# X_TRACK_MCU_V3_1.net
KiCad netlist of a schematic drawn in Altium Designer
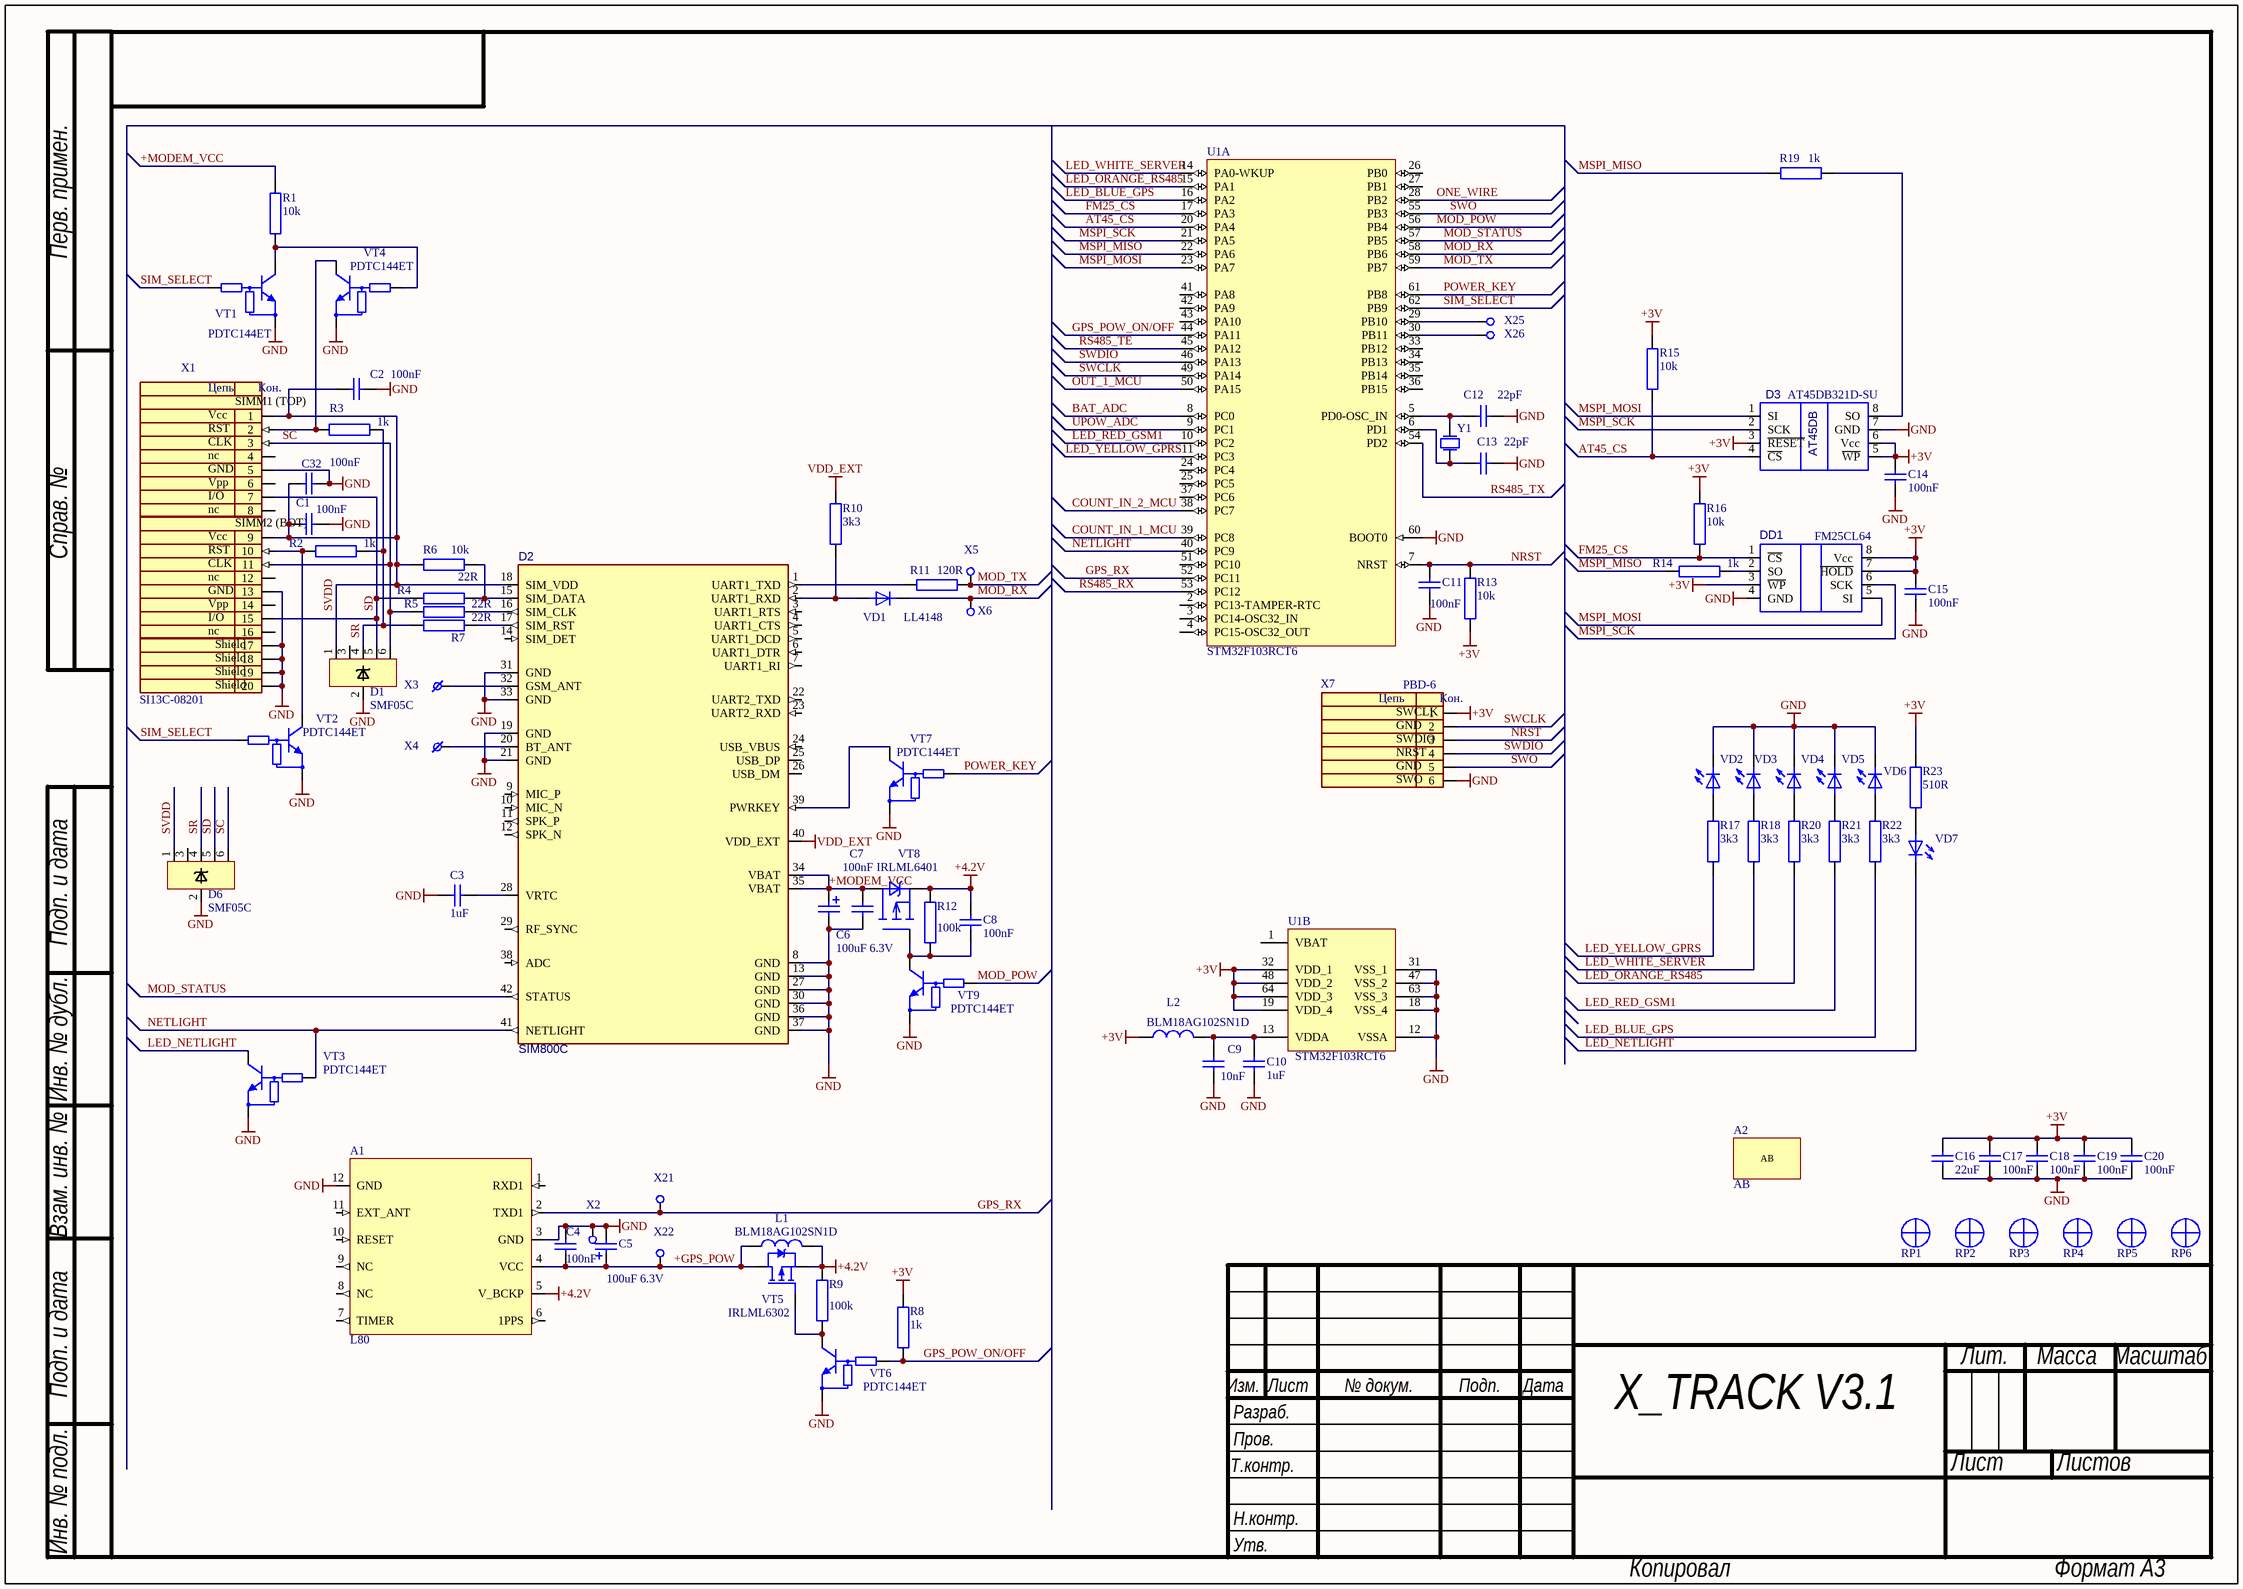
[diagram p0: X_TRACK_MCU V3.1.SchDoc]

(export (version "E")
  (design (tool "Eeschema 10.0.6"))
  (components
    (comp (ref "A1")
      (value "L80")
      (footprint "L80")
      (description "Quectel  Slim GPS Module  Integrated Patch Antenna")
      (fields (field (name "MANUFACTURER") "Quectel"))
      (libsource (lib "Ethernet_new_v000") (part "L80"))
    )
    (comp (ref "A2") (value "AB") (footprint "AB") (libsource (lib "Ethernet_new_v000") (part "AB")))
    (comp (ref "C1")
      (value "100nF")
      (footprint "CC0805")
      (description "Capacitor SMD 0805 X7R 100nF 20% 50V")
      (fields (field (name "MANUFACTURER") "Hitano") (field (name "Comment") "CC0805_100nF"))
      (libsource (lib "Ethernet_new_v000") (part "CC0805_100nF"))
    )
    (comp (ref "C2")
      (value "100nF")
      (footprint "CC0603")
      (description "Capacitor SMD 0603 X7R 100nF 20% 50V")
      (fields (field (name "MANUFACTURER") "Hitano") (field (name "Comment") "CC0603_100nF"))
      (libsource (lib "Ethernet_new_v000") (part "CC0603_100nF"))
    )
    (comp (ref "C3")
      (value "1uF")
      (footprint "CC0603")
      (description "Capacitor SMD 0603 X7R 1uF 20% 10V")
      (fields (field (name "MANUFACTURER") "Hitano") (field (name "Comment") "CC0603_1uF"))
      (libsource (lib "Ethernet_new_v000") (part "CC0603_1uF"))
    )
    (comp (ref "C4")
      (value "100nF")
      (footprint "CC0603")
      (description "Capacitor SMD 0603 X7R 100nF 20% 50V")
      (fields (field (name "MANUFACTURER") "Hitano") (field (name "Comment") "CC0603_100nF"))
      (libsource (lib "Ethernet_new_v000") (part "CC0603_100nF"))
    )
    (comp (ref "C5")
      (value "100uF 6.3V")
      (footprint "6032_TC")
      (description "Capacitor tantall")
      (fields (field (name "MANUFACTURER") "AVX") (field (name "Comment") "C_TAJ 100uF 6.3V C"))
      (libsource (lib "Ethernet_new_v000") (part "C_TAJ 100uF 6.3V C"))
    )
    (comp (ref "C6")
      (value "100uF 6.3V")
      (footprint "6032_TC")
      (description "Capacitor tantall")
      (fields (field (name "MANUFACTURER") "AVX") (field (name "Comment") "C_TAJ 100uF 6.3V C"))
      (libsource (lib "Ethernet_new_v000") (part "C_TAJ 100uF 6.3V C"))
    )
    (comp (ref "C7")
      (value "100nF")
      (footprint "CC0603")
      (description "Capacitor SMD 0603 X7R 100nF 20% 50V")
      (fields (field (name "MANUFACTURER") "Hitano") (field (name "Comment") "CC0603_100nF"))
      (libsource (lib "Ethernet_new_v000") (part "CC0603_100nF"))
    )
    (comp (ref "C8")
      (value "100nF")
      (footprint "CC0603")
      (description "Capacitor SMD 0603 X7R 100nF 20% 50V")
      (fields (field (name "MANUFACTURER") "Hitano") (field (name "Comment") "CC0603_100nF"))
      (libsource (lib "Ethernet_new_v000") (part "CC0603_100nF"))
    )
    (comp (ref "C9")
      (value "10nF")
      (footprint "CC0603")
      (description "Capacitor SMD 0603 X7R 10nF 20% 50V")
      (fields (field (name "MANUFACTURER") "Hitano") (field (name "Comment") "CC0603_10nF"))
      (libsource (lib "Ethernet_new_v000") (part "CC0603_10nF"))
    )
    (comp (ref "C10")
      (value "1uF")
      (footprint "CC0805")
      (description "Capacitor SMD 0805 Y5V 1uF 20% 16V")
      (fields (field (name "MANUFACTURER") "Hitano") (field (name "Comment") "CC0805_1uF"))
      (libsource (lib "Ethernet_new_v000") (part "CC0805_1uF"))
    )
    (comp (ref "C11")
      (value "100nF")
      (footprint "CC0603")
      (description "Capacitor SMD 0603 X7R 100nF 20% 50V")
      (fields (field (name "MANUFACTURER") "Hitano") (field (name "Comment") "CC0603_100nF"))
      (libsource (lib "Ethernet_new_v000") (part "CC0603_100nF"))
    )
    (comp (ref "C12")
      (value "22pF")
      (footprint "CC0603")
      (description "Capacitor SMD 0603 NPO 22pF 5% 50V")
      (fields (field (name "MANUFACTURER") "Hitano") (field (name "Comment") "CC0603_22pF"))
      (libsource (lib "Ethernet_new_v000") (part "CC0603_22pF"))
    )
    (comp (ref "C13")
      (value "22pF")
      (footprint "CC0603")
      (description "Capacitor SMD 0603 NPO 22pF 5% 50V")
      (fields (field (name "MANUFACTURER") "Hitano") (field (name "Comment") "CC0603_22pF"))
      (libsource (lib "Ethernet_new_v000") (part "CC0603_22pF"))
    )
    (comp (ref "C14")
      (value "100nF")
      (footprint "CC0603")
      (description "Capacitor SMD 0603 X7R 100nF 20% 50V")
      (fields (field (name "MANUFACTURER") "Hitano") (field (name "Comment") "CC0603_100nF"))
      (libsource (lib "Ethernet_new_v000") (part "CC0603_100nF"))
    )
    (comp (ref "C15")
      (value "100nF")
      (footprint "CC0603")
      (description "Capacitor SMD 0603 X7R 100nF 20% 50V")
      (fields (field (name "MANUFACTURER") "Hitano") (field (name "Comment") "CC0603_100nF"))
      (libsource (lib "Ethernet_new_v000") (part "CC0603_100nF"))
    )
    (comp (ref "C16")
      (value "22uF")
      (footprint "CC0805")
      (description "Capacitor SMD 0805 Y5V 10uF 20% 16V")
      (fields (field (name "MANUFACTURER") "Hitano") (field (name "Comment") "CC0805_10uF"))
      (libsource (lib "Ethernet_new_v000") (part "CC0805_10uF"))
    )
    (comp (ref "C17")
      (value "100nF")
      (footprint "CC0603")
      (description "Capacitor SMD 0603 X7R 100nF 20% 50V")
      (fields (field (name "MANUFACTURER") "Hitano") (field (name "Comment") "CC0603_100nF"))
      (libsource (lib "Ethernet_new_v000") (part "CC0603_100nF"))
    )
    (comp (ref "C18")
      (value "100nF")
      (footprint "CC0603")
      (description "Capacitor SMD 0603 X7R 100nF 20% 50V")
      (fields (field (name "MANUFACTURER") "Hitano") (field (name "Comment") "CC0603_100nF"))
      (libsource (lib "Ethernet_new_v000") (part "CC0603_100nF"))
    )
    (comp (ref "C19")
      (value "100nF")
      (footprint "CC0603")
      (description "Capacitor SMD 0603 X7R 100nF 20% 50V")
      (fields (field (name "MANUFACTURER") "Hitano") (field (name "Comment") "CC0603_100nF"))
      (libsource (lib "Ethernet_new_v000") (part "CC0603_100nF"))
    )
    (comp (ref "C20")
      (value "100nF")
      (footprint "CC0603")
      (description "Capacitor SMD 0603 X7R 100nF 20% 50V")
      (fields (field (name "MANUFACTURER") "Hitano") (field (name "Comment") "CC0603_100nF"))
      (libsource (lib "Ethernet_new_v000") (part "CC0603_100nF"))
    )
    (comp (ref "C32")
      (value "100nF")
      (footprint "CC0603")
      (description "Capacitor SMD 0603 X7R 100nF 20% 50V")
      (fields (field (name "MANUFACTURER") "Hitano") (field (name "Comment") "CC0603_100nF"))
      (libsource (lib "Ethernet_new_v000") (part "CC0603_100nF"))
    )
    (comp (ref "D1")
      (value "SMF05C")
      (footprint "sc70-6")
      (description "TVS Diode Array For ESD and Latch-Up Protection")
      (fields (field (name "MANUFACTURER") "Semtech"))
      (libsource (lib "Ethernet_new_v000") (part "SMF05C"))
    )
    (comp (ref "D2")
      (value "SIM800C")
      (footprint "SIM800C")
      (fields (field (name "MANUFACTURER") "SIMCOM"))
      (libsource (lib "Ethernet_new_v000") (part "SIM800C"))
    )
    (comp (ref "D3")
      (value "AT45DB321D-SU")
      (footprint "8S2_N_2")
      (description "AT45DB")
      (libsource (lib "V1.5") (part "AT45DB"))
    )
    (comp (ref "D6")
      (value "SMF05C")
      (footprint "sc70-6")
      (description "TVS Diode Array For ESD and Latch-Up Protection")
      (fields (field (name "MANUFACTURER") "Semtech"))
      (libsource (lib "Ethernet_new_v000") (part "SMF05C"))
    )
    (comp (ref "DD1") (value "FM25CL64") (footprint "SO8") (libsource (lib "X_TRACK V1") (part "FM25CL64")))
    (comp (ref "L1")
      (value "BLM18AG102SN1D")
      (footprint "BLM18")
      (description "SMD inductance 750mA")
      (fields (field (name "MANUFACTURER") "Samsung") (field (name "Comment") "L_CIC10P601NC"))
      (libsource (lib "Ethernet_new_v000") (part "L_CIC10P601NC"))
    )
    (comp (ref "L2")
      (value "BLM18AG102SN1D")
      (footprint "BLM18")
      (description "SMD inductance 750mA")
      (fields (field (name "MANUFACTURER") "Samsung") (field (name "Comment") "L_CIC10P601NC"))
      (libsource (lib "Ethernet_new_v000") (part "L_CIC10P601NC"))
    )
    (comp (ref "R1")
      (value "10k")
      (footprint "RC0603")
      (description "Resistor  SMD RC0603 5% 10k")
      (fields (field (name "MANUFACTURER") "Hitano") (field (name "Comment") "RC0603 10k"))
      (libsource (lib "Ethernet_new_v000") (part "RC0603 10k"))
    )
    (comp (ref "R2")
      (value "1k")
      (footprint "RC0603")
      (description "Resistor  SMD 0603  5% 1k")
      (fields (field (name "MANUFACTURER") "Hitano") (field (name "Comment") "RC0603 1k"))
      (libsource (lib "Ethernet_new_v000") (part "RC0603 1k"))
    )
    (comp (ref "R3")
      (value "1k")
      (footprint "RC0603")
      (description "Resistor  SMD 0603  5% 1k")
      (fields (field (name "MANUFACTURER") "Hitano") (field (name "Comment") "RC0603 1k"))
      (libsource (lib "Ethernet_new_v000") (part "RC0603 1k"))
    )
    (comp (ref "R4")
      (value "22R")
      (footprint "RC0603")
      (description "Resistor  SMD 0603 5% 22R")
      (fields (field (name "MANUFACTURER") "Hitano") (field (name "Comment") "RC0603 22R"))
      (libsource (lib "Ethernet_new_v000") (part "RC0603 22R"))
    )
    (comp (ref "R5")
      (value "22R")
      (footprint "RC0603")
      (description "Resistor  SMD 0603 5% 22R")
      (fields (field (name "MANUFACTURER") "Hitano") (field (name "Comment") "RC0603 22R"))
      (libsource (lib "Ethernet_new_v000") (part "RC0603 22R"))
    )
    (comp (ref "R6")
      (value "10k")
      (footprint "RC0603")
      (description "Resistor  SMD RC0603 5% 10k")
      (fields (field (name "MANUFACTURER") "Hitano") (field (name "Comment") "RC0603 10k"))
      (libsource (lib "Ethernet_new_v000") (part "RC0603 10k"))
    )
    (comp (ref "R7")
      (value "22R")
      (footprint "RC0603")
      (description "Resistor  SMD 0603 5% 22R")
      (fields (field (name "MANUFACTURER") "Hitano") (field (name "Comment") "RC0603 22R"))
      (libsource (lib "Ethernet_new_v000") (part "RC0603 22R"))
    )
    (comp (ref "R8")
      (value "1k")
      (footprint "RC0603")
      (description "Resistor  SMD 0603  5% 1k")
      (fields (field (name "MANUFACTURER") "Hitano") (field (name "Comment") "RC0603 1k"))
      (libsource (lib "Ethernet_new_v000") (part "RC0603 1k"))
    )
    (comp (ref "R9")
      (value "100k")
      (footprint "RC0603")
      (description "Resistor  SMD 0603 5% 100k")
      (fields (field (name "MANUFACTURER") "Hitano") (field (name "Comment") "RC0603 100k"))
      (libsource (lib "Ethernet_new_v000") (part "RC0603 100k"))
    )
    (comp (ref "R10")
      (value "3k3")
      (footprint "RC0603")
      (description "Resistor  SMD RC0603 5% 10k")
      (fields (field (name "MANUFACTURER") "Hitano") (field (name "Comment") "RC0603 10k"))
      (libsource (lib "Ethernet_new_v000") (part "RC0603 10k"))
    )
    (comp (ref "R11")
      (value "120R")
      (footprint "RC0603")
      (description "Resistor  SMD 0603 5% 120R")
      (fields (field (name "MANUFACTURER") "Hitano") (field (name "Comment") "RC0603 120R"))
      (libsource (lib "Ethernet_new_v000") (part "RC0603 120R"))
    )
    (comp (ref "R12")
      (value "100k")
      (footprint "RC0603")
      (description "Resistor  SMD 0603 5% 100k")
      (fields (field (name "MANUFACTURER") "Hitano") (field (name "Comment") "RC0603 100k"))
      (libsource (lib "Ethernet_new_v000") (part "RC0603 100k"))
    )
    (comp (ref "R13")
      (value "10k")
      (footprint "RC0603")
      (description "Resistor  SMD RC0603 5% 10k")
      (fields (field (name "MANUFACTURER") "Hitano") (field (name "Comment") "RC0603 10k"))
      (libsource (lib "Ethernet_new_v000") (part "RC0603 10k"))
    )
    (comp (ref "R14")
      (value "1k")
      (footprint "RC0603")
      (description "Resistor  SMD 0603  5% 1k")
      (fields (field (name "MANUFACTURER") "Hitano") (field (name "Comment") "RC0603 1k"))
      (libsource (lib "Ethernet_new_v000") (part "RC0603 1k"))
    )
    (comp (ref "R15")
      (value "10k")
      (footprint "RC0603")
      (description "Resistor  SMD RC0603 5% 10k")
      (fields (field (name "MANUFACTURER") "Hitano") (field (name "Comment") "RC0603 10k"))
      (libsource (lib "Ethernet_new_v000") (part "RC0603 10k"))
    )
    (comp (ref "R16")
      (value "10k")
      (footprint "RC0603")
      (description "Resistor  SMD RC0603 5% 10k")
      (fields (field (name "MANUFACTURER") "Hitano") (field (name "Comment") "RC0603 10k"))
      (libsource (lib "Ethernet_new_v000") (part "RC0603 10k"))
    )
    (comp (ref "R17")
      (value "3k3")
      (footprint "RC0805")
      (description "Resistor  SMD 0805 5% 1k")
      (fields (field (name "MANUFACTURER") "Hitano") (field (name "Comment") "RC0805 1k"))
      (libsource (lib "Ethernet_new_v000") (part "RC0805 1k"))
    )
    (comp (ref "R18")
      (value "3k3")
      (footprint "RC0603")
      (description "Resistor  SMD 0603 5% 300R")
      (fields (field (name "MANUFACTURER") "Hitano") (field (name "Comment") "RC0603 300R"))
      (libsource (lib "Ethernet_new_v000") (part "RC0603 300R"))
    )
    (comp (ref "R19")
      (value "1k")
      (footprint "RC0603")
      (description "Resistor  SMD 0603  5% 1k")
      (fields (field (name "MANUFACTURER") "Hitano") (field (name "Comment") "RC0603 1k"))
      (libsource (lib "Ethernet_new_v000") (part "RC0603 1k"))
    )
    (comp (ref "R20")
      (value "3k3")
      (footprint "RC0603")
      (description "Resistor  SMD 0603 5% 300R")
      (fields (field (name "MANUFACTURER") "Hitano") (field (name "Comment") "RC0603 300R"))
      (libsource (lib "Ethernet_new_v000") (part "RC0603 300R"))
    )
    (comp (ref "R21")
      (value "3k3")
      (footprint "RC0603")
      (description "Resistor  SMD 0603 5% 300R")
      (fields (field (name "MANUFACTURER") "Hitano") (field (name "Comment") "RC0603 300R"))
      (libsource (lib "Ethernet_new_v000") (part "RC0603 300R"))
    )
    (comp (ref "R22")
      (value "3k3")
      (footprint "RC0603")
      (description "Resistor  SMD 0603 5% 300R")
      (fields (field (name "MANUFACTURER") "Hitano") (field (name "Comment") "RC0603 300R"))
      (libsource (lib "Ethernet_new_v000") (part "RC0603 300R"))
    )
    (comp (ref "R23")
      (value "510R")
      (footprint "RC0603")
      (description "Resistor  SMD 0603 5% 300R")
      (fields (field (name "MANUFACTURER") "Hitano") (field (name "Comment") "RC0603 300R"))
      (libsource (lib "Ethernet_new_v000") (part "RC0603 300R"))
    )
    (comp (ref "RP1")
      (value "Reper point")
      (footprint "REPER_1_2")
      (description "Reper point 1_2 mm")
      (libsource (lib "Ethernet_new_v000") (part "Reper point"))
    )
    (comp (ref "RP2")
      (value "Reper point")
      (footprint "REPER_1_2")
      (description "Reper point 1_2 mm")
      (libsource (lib "Ethernet_new_v000") (part "Reper point"))
    )
    (comp (ref "RP3")
      (value "Reper point")
      (footprint "REPER_1_2")
      (description "Reper point 1_2 mm")
      (libsource (lib "Ethernet_new_v000") (part "Reper point"))
    )
    (comp (ref "RP4")
      (value "Reper point")
      (footprint "REPER_1_2")
      (description "Reper point 1_2 mm")
      (libsource (lib "Ethernet_new_v000") (part "Reper point"))
    )
    (comp (ref "RP5")
      (value "Reper point")
      (footprint "REPER_1_2")
      (description "Reper point 1_2 mm")
      (libsource (lib "Ethernet_new_v000") (part "Reper point"))
    )
    (comp (ref "RP6")
      (value "Reper point")
      (footprint "REPER_1_2")
      (description "Reper point 1_2 mm")
      (libsource (lib "Ethernet_new_v000") (part "Reper point"))
    )
    (comp (ref "U1")
      (value "STM32F103RCT6")
      (footprint "LQFP64_N")
      (libsource (lib "STMicroelectronics STM32 F1") (part "STM32F103RCT6"))
    )
    (comp (ref "VD1")
      (value "LL4148")
      (footprint "SOD80D_C")
      (description "SMD Diod BAS85")
      (fields (field (name "MANUFACTURER") "Philips/NXP") (field (name "Comment") "BAS85"))
      (libsource (lib "Ethernet_new_v000") (part "BAS85"))
    )
    (comp (ref "VD2")
      (value "LED_KP-2012EC(0805)_1")
      (footprint "KP-2012EC")
      (description "2.0mmx1.25mm SMT LED,1.1mm thickness High Efficiency Red")
      (fields (field (name "MANUFACTURER") "Kingbright"))
      (libsource (lib "Ethernet_new_v000") (part "LED_KP-2012EC(0805)_1"))
    )
    (comp (ref "VD3")
      (value "LED_KP-2012EC(0805)_1")
      (footprint "KP-2012EC")
      (description "2.0mmx1.25mm SMT LED,1.1mm thickness High Efficiency Red")
      (fields (field (name "MANUFACTURER") "Kingbright"))
      (libsource (lib "Ethernet_new_v000") (part "LED_KP-2012EC(0805)_1"))
    )
    (comp (ref "VD4")
      (value "LED_KP-2012EC(0805)_1")
      (footprint "KP-2012EC")
      (description "2.0mmx1.25mm SMT LED,1.1mm thickness High Efficiency Red")
      (fields (field (name "MANUFACTURER") "Kingbright"))
      (libsource (lib "Ethernet_new_v000") (part "LED_KP-2012EC(0805)_1"))
    )
    (comp (ref "VD5")
      (value "LED_KP-2012EC(0805)_1")
      (footprint "KP-2012EC")
      (description "2.0mmx1.25mm SMT LED,1.1mm thickness High Efficiency Red")
      (fields (field (name "MANUFACTURER") "Kingbright"))
      (libsource (lib "Ethernet_new_v000") (part "LED_KP-2012EC(0805)_1"))
    )
    (comp (ref "VD6")
      (value "LED_KP-2012EC(0805)_1")
      (footprint "KP-2012EC")
      (description "2.0mmx1.25mm SMT LED,1.1mm thickness High Efficiency Red")
      (fields (field (name "MANUFACTURER") "Kingbright"))
      (libsource (lib "Ethernet_new_v000") (part "LED_KP-2012EC(0805)_1"))
    )
    (comp (ref "VD7")
      (value "LED_KP-2012EC(0805)_1")
      (footprint "KP-2012EC")
      (description "2.0mmx1.25mm SMT LED,1.1mm thickness High Efficiency Red")
      (fields (field (name "MANUFACTURER") "Kingbright"))
      (libsource (lib "Ethernet_new_v000") (part "LED_KP-2012EC(0805)_1"))
    )
    (comp (ref "VT1")
      (value "PDTC144ET")
      (footprint "SOT23")
      (description "NPN Digital transistor with bult-in resistor 2k  100mA/50V")
      (fields (field (name "MANUFACTURER") "NXP Semiconductors") (field (name "Comment") "PDTC123ET"))
      (libsource (lib "") (part "PDTC123ET_1"))
    )
    (comp (ref "VT2")
      (value "PDTC144ET")
      (footprint "SOT23")
      (description "NPN Digital transistor with bult-in resistor 2k  100mA/50V")
      (fields (field (name "MANUFACTURER") "NXP Semiconductors") (field (name "Comment") "PDTC123ET"))
      (libsource (lib "") (part "PDTC123ET_1"))
    )
    (comp (ref "VT3")
      (value "PDTC144ET")
      (footprint "SOT23")
      (description "NPN Digital transistor with bult-in resistor 2k  100mA/50V")
      (fields (field (name "MANUFACTURER") "NXP Semiconductors") (field (name "Comment") "PDTC123ET"))
      (libsource (lib "Ethernet_new_v000") (part "PDTC123ET"))
    )
    (comp (ref "VT4")
      (value "PDTC144ET")
      (footprint "SOT23")
      (description "NPN Digital transistor with bult-in resistor 2k  100mA/50V")
      (fields (field (name "MANUFACTURER") "NXP Semiconductors") (field (name "Comment") "PDTC123ET"))
      (libsource (lib "Ethernet_new_v000") (part "PDTC123ET"))
    )
    (comp (ref "VT5")
      (value "IRLML6302")
      (footprint "SOT23")
      (description "P-Channel Power MOSFET 20V 0.78A(25`C)")
      (fields (field (name "MANUFACTURER") "International Rectifier"))
      (libsource (lib "Ethernet_new_v000") (part "IRLML6302"))
    )
    (comp (ref "VT6")
      (value "PDTC144ET")
      (footprint "SOT23")
      (description "NPN Digital transistor with bult-in resistor 2k  100mA/50V")
      (fields (field (name "MANUFACTURER") "NXP Semiconductors") (field (name "Comment") "PDTC123ET"))
      (libsource (lib "Ethernet_new_v000") (part "PDTC123ET"))
    )
    (comp (ref "VT7")
      (value "PDTC144ET")
      (footprint "SOT23")
      (description "NPN Digital transistor with bult-in resistor 2k  100mA/50V")
      (fields (field (name "MANUFACTURER") "NXP Semiconductors") (field (name "Comment") "PDTC123ET"))
      (libsource (lib "Ethernet_new_v000") (part "PDTC123ET"))
    )
    (comp (ref "VT8") (value "IRLML6401") (footprint "SOT23") (libsource (lib "V1.5") (part "IRLML6401")))
    (comp (ref "VT9")
      (value "PDTC144ET")
      (footprint "SOT23")
      (description "NPN Digital transistor with bult-in resistor 2k  100mA/50V")
      (fields (field (name "MANUFACTURER") "NXP Semiconductors") (field (name "Comment") "PDTC123ET"))
      (libsource (lib "Ethernet_new_v000") (part "PDTC123ET"))
    )
    (comp (ref "X1")
      (value "SI13С-08201")
      (footprint "SI13C-08201")
      (description "Dual SIM Card Connector h=3.0mm max")
      (fields (field (name "MANUFACTURER") "ATOM"))
      (libsource (lib "Ethernet_new_v000") (part "SI13С-08201"))
    )
    (comp (ref "X2")
      (value "Con 1")
      (footprint "TP_0.8/1.5")
      (description "Contact")
      (libsource (lib "Ethernet_new_v000") (part "Con 1"))
    )
    (comp (ref "X3")
      (value "Con_1")
      (footprint "TP_1.5/2.5")
      (description "Contact")
      (libsource (lib "Ethernet_new_v000") (part "Con_1"))
    )
    (comp (ref "X4")
      (value "Con_1")
      (footprint "TP_1/2")
      (description "Contact")
      (libsource (lib "Ethernet_new_v000") (part "Con_1"))
    )
    (comp (ref "X5")
      (value "Con 1")
      (footprint "TP_0.8/1.5")
      (description "Contact")
      (libsource (lib "Ethernet_new_v000") (part "Con 1"))
    )
    (comp (ref "X6")
      (value "Con 1")
      (footprint "TP_0.8/1.5")
      (description "Contact")
      (libsource (lib "Ethernet_new_v000") (part "Con 1"))
    )
    (comp (ref "X7")
      (value "PBD-6")
      (footprint "PLS6")
      (description "CON_1x6")
      (fields (field (name "MANUFACTURER") "Amtek") (field (name "Comment") "CON_1x6_"))
      (libsource (lib "X_TRACK V1") (part "CON_1x6_"))
    )
    (comp (ref "X21")
      (value "Con 1")
      (footprint "TP_0.8/1.5")
      (description "Contact")
      (libsource (lib "Ethernet_new_v000") (part "Con 1"))
    )
    (comp (ref "X22")
      (value "Con 1")
      (footprint "TP_0.8/1.5")
      (description "Contact")
      (libsource (lib "Ethernet_new_v000") (part "Con 1"))
    )
    (comp (ref "X25")
      (value "Con 1")
      (footprint "TP_0.5/1.0 - without silkscreen")
      (description "Contact")
      (libsource (lib "Ethernet_new_v000") (part "Con 1"))
    )
    (comp (ref "X26")
      (value "Con 1")
      (footprint "TP_0.5/1.0 - without silkscreen")
      (description "Contact")
      (libsource (lib "Ethernet_new_v000") (part "Con 1"))
    )
    (comp (ref "Y1")
      (value "XTAL")
      (footprint "CRYSTAL")
      (description "Crystal Oscillator")
      (fields (field (name "MANUFACTURER") "Jauch"))
      (libsource (lib "Ethernet_new_v000") (part "XTAL"))
    )
  )
  (nets
    (net (code "1") (name "+3V") (class "Default")
      (node (ref "C14") (pin "2") (pinfunction "2_2") (pintype "passive"))
      (node (ref "C15") (pin "2") (pinfunction "2_2") (pintype "passive"))
      (node (ref "C16") (pin "2") (pinfunction "2_2") (pintype "passive"))
      (node (ref "C17") (pin "2") (pinfunction "2_2") (pintype "passive"))
      (node (ref "C18") (pin "2") (pinfunction "2_2") (pintype "passive"))
      (node (ref "C19") (pin "2") (pinfunction "2_2") (pintype "passive"))
      (node (ref "C20") (pin "2") (pinfunction "2_2") (pintype "passive"))
      (node (ref "D3") (pin "3") (pinfunction "~{RESET}_3") (pintype "passive"))
      (node (ref "D3") (pin "5") (pinfunction "~{WP}_5") (pintype "passive"))
      (node (ref "D3") (pin "6") (pinfunction "Vcc_6") (pintype "passive"))
      (node (ref "DD1") (pin "3") (pinfunction "~{WP}_3") (pintype "passive"))
      (node (ref "DD1") (pin "7") (pinfunction "~{HOLD}_7") (pintype "passive"))
      (node (ref "DD1") (pin "8") (pinfunction "Vcc_8") (pintype "passive"))
      (node (ref "L2") (pin "1") (pinfunction "1_1") (pintype "passive"))
      (node (ref "R13") (pin "2") (pinfunction "2_2") (pintype "passive"))
      (node (ref "R15") (pin "2") (pinfunction "2_2") (pintype "passive"))
      (node (ref "R16") (pin "2") (pinfunction "2_2") (pintype "passive"))
      (node (ref "R23") (pin "2") (pinfunction "2_2") (pintype "passive"))
      (node (ref "R8") (pin "2") (pinfunction "2_2") (pintype "passive"))
      (node (ref "U1") (pin "19") (pinfunction "VDD_4_19") (pintype "power_in"))
      (node (ref "U1") (pin "32") (pinfunction "VDD_1_32") (pintype "power_in"))
      (node (ref "U1") (pin "48") (pinfunction "VDD_2_48") (pintype "power_in"))
      (node (ref "U1") (pin "64") (pinfunction "VDD_3_64") (pintype "power_in"))
      (node (ref "X7") (pin "1") (pinfunction "1_1") (pintype "passive"))
    )
    (net (code "2") (name "+4.2V") (class "Default")
      (node (ref "A1") (pin "5") (pinfunction "V_BCKP_5") (pintype "power_in"))
      (node (ref "C8") (pin "2") (pinfunction "2_2") (pintype "passive"))
      (node (ref "L1") (pin "2") (pinfunction "2_2") (pintype "passive"))
      (node (ref "R12") (pin "2") (pinfunction "2_2") (pintype "passive"))
      (node (ref "R9") (pin "2") (pinfunction "2_2") (pintype "passive"))
      (node (ref "VT5") (pin "2") (pinfunction "S_2") (pintype "passive"))
      (node (ref "VT8") (pin "2") (pinfunction "S_2") (pintype "passive"))
    )
    (net (code "3") (name "/+GPS_POW") (class "Default")
      (node (ref "A1") (pin "4") (pinfunction "VCC_4") (pintype "power_in"))
      (node (ref "C4") (pin "2") (pinfunction "2_2") (pintype "passive"))
      (node (ref "C5") (pin "1") (pinfunction "1_1") (pintype "passive"))
      (node (ref "L1") (pin "1") (pinfunction "1_1") (pintype "passive"))
      (node (ref "VT5") (pin "3") (pinfunction "D_3") (pintype "passive"))
      (node (ref "X22") (pin "1") (pinfunction "1_1") (pintype "passive"))
    )
    (net (code "4") (name "/+MODEM_VCC") (class "Default")
      (node (ref "C6") (pin "1") (pinfunction "1_1") (pintype "passive"))
      (node (ref "C7") (pin "2") (pinfunction "2_2") (pintype "passive"))
      (node (ref "D2") (pin "34") (pinfunction "VBAT_34") (pintype "power_in"))
      (node (ref "D2") (pin "35") (pinfunction "VBAT_35") (pintype "power_in"))
      (node (ref "R1") (pin "1") (pinfunction "1_1") (pintype "passive"))
      (node (ref "VT8") (pin "3") (pinfunction "D_3") (pintype "passive"))
    )
    (net (code "5") (name "/AT45_CS") (class "Default")
      (node (ref "D3") (pin "4") (pinfunction "~{CS}_4") (pintype "passive"))
      (node (ref "R15") (pin "1") (pinfunction "1_1") (pintype "passive"))
      (node (ref "U1") (pin "20") (pinfunction "PA4_20") (pintype "bidirectional"))
    )
    (net (code "6") (name "/BAT_ADC") (class "Default")
      (node (ref "U1") (pin "8") (pinfunction "PC0_8") (pintype "bidirectional"))
    )
    (net (code "7") (name "/COUNT_IN_1_MCU") (class "Default")
      (node (ref "U1") (pin "39") (pinfunction "PC8_39") (pintype "bidirectional"))
    )
    (net (code "8") (name "/COUNT_IN_2_MCU") (class "Default")
      (node (ref "U1") (pin "38") (pinfunction "PC7_38") (pintype "bidirectional"))
    )
    (net (code "9") (name "/FM25_CS") (class "Default")
      (node (ref "DD1") (pin "1") (pinfunction "~{CS}_1") (pintype "passive"))
      (node (ref "R16") (pin "1") (pinfunction "1_1") (pintype "passive"))
      (node (ref "U1") (pin "17") (pinfunction "PA3_17") (pintype "bidirectional"))
    )
    (net (code "10") (name "/GPS_POW_ON{slash}OFF") (class "Default")
      (node (ref "R8") (pin "1") (pinfunction "1_1") (pintype "passive"))
      (node (ref "U1") (pin "44") (pinfunction "PA11_44") (pintype "bidirectional"))
      (node (ref "VT6") (pin "1") (pinfunction "B_1") (pintype "passive"))
    )
    (net (code "11") (name "/GPS_RX") (class "Default")
      (node (ref "A1") (pin "2") (pinfunction "TXD1_2") (pintype "output"))
      (node (ref "U1") (pin "52") (pinfunction "PC11_52") (pintype "bidirectional"))
      (node (ref "X21") (pin "1") (pinfunction "1_1") (pintype "passive"))
    )
    (net (code "12") (name "/LED_BLUE_GPS") (class "Default")
      (node (ref "R22") (pin "1") (pinfunction "1_1") (pintype "passive"))
      (node (ref "U1") (pin "16") (pinfunction "PA2_16") (pintype "bidirectional"))
    )
    (net (code "13") (name "/LED_NETLIGHT") (class "Default")
      (node (ref "VD7") (pin "2") (pinfunction "K_2") (pintype "passive"))
      (node (ref "VT3") (pin "3") (pinfunction "C_3") (pintype "passive"))
    )
    (net (code "14") (name "/LED_ORANGE_RS485") (class "Default")
      (node (ref "R20") (pin "1") (pinfunction "1_1") (pintype "passive"))
      (node (ref "U1") (pin "15") (pinfunction "PA1_15") (pintype "bidirectional"))
    )
    (net (code "15") (name "/LED_RED_GSM1") (class "Default")
      (node (ref "R21") (pin "1") (pinfunction "1_1") (pintype "passive"))
      (node (ref "U1") (pin "10") (pinfunction "PC2_10") (pintype "bidirectional"))
    )
    (net (code "16") (name "/LED_WHITE_SERVER") (class "Default")
      (node (ref "R18") (pin "1") (pinfunction "1_1") (pintype "passive"))
      (node (ref "U1") (pin "14") (pinfunction "PA0-WKUP_14") (pintype "bidirectional"))
    )
    (net (code "17") (name "/LED_YELLOW_GPRS") (class "Default")
      (node (ref "R17") (pin "1") (pinfunction "1_1") (pintype "passive"))
      (node (ref "U1") (pin "11") (pinfunction "PC3_11") (pintype "bidirectional"))
    )
    (net (code "18") (name "/MOD_POW") (class "Default")
      (node (ref "U1") (pin "56") (pinfunction "PB4_56") (pintype "bidirectional"))
      (node (ref "VT9") (pin "1") (pinfunction "B_1") (pintype "passive"))
    )
    (net (code "19") (name "/MOD_RX") (class "Default")
      (node (ref "U1") (pin "58") (pinfunction "PB6_58") (pintype "bidirectional"))
      (node (ref "VD1") (pin "2") (pinfunction "K_2") (pintype "passive"))
      (node (ref "X6") (pin "1") (pinfunction "1_1") (pintype "passive"))
    )
    (net (code "20") (name "/MOD_STATUS") (class "Default")
      (node (ref "D2") (pin "42") (pinfunction "STATUS_42") (pintype "output"))
      (node (ref "U1") (pin "57") (pinfunction "PB5_57") (pintype "bidirectional"))
    )
    (net (code "21") (name "/MOD_TX") (class "Default")
      (node (ref "R11") (pin "1") (pinfunction "1_1") (pintype "passive"))
      (node (ref "U1") (pin "59") (pinfunction "PB7_59") (pintype "bidirectional"))
      (node (ref "X5") (pin "1") (pinfunction "1_1") (pintype "passive"))
    )
    (net (code "22") (name "/MSPI_MISO") (class "Default")
      (node (ref "R14") (pin "1") (pinfunction "1_1") (pintype "passive"))
      (node (ref "R19") (pin "1") (pinfunction "1_1") (pintype "passive"))
      (node (ref "U1") (pin "22") (pinfunction "PA6_22") (pintype "bidirectional"))
    )
    (net (code "23") (name "/MSPI_MOSI") (class "Default")
      (node (ref "D3") (pin "1") (pinfunction "SI_1") (pintype "passive"))
      (node (ref "DD1") (pin "5") (pinfunction "SI_5") (pintype "passive"))
      (node (ref "U1") (pin "23") (pinfunction "PA7_23") (pintype "bidirectional"))
    )
    (net (code "24") (name "/MSPI_SCK") (class "Default")
      (node (ref "D3") (pin "2") (pinfunction "SCK_2") (pintype "passive"))
      (node (ref "DD1") (pin "6") (pinfunction "SCK_6") (pintype "passive"))
      (node (ref "U1") (pin "21") (pinfunction "PA5_21") (pintype "bidirectional"))
    )
    (net (code "25") (name "/NETLIGHT") (class "Default")
      (node (ref "D2") (pin "41") (pinfunction "NETLIGHT_41") (pintype "output"))
      (node (ref "U1") (pin "40") (pinfunction "PC9_40") (pintype "bidirectional"))
      (node (ref "VT3") (pin "1") (pinfunction "B_1") (pintype "passive"))
    )
    (net (code "26") (name "/NRST") (class "Default")
      (node (ref "C11") (pin "2") (pinfunction "2_2") (pintype "passive"))
      (node (ref "R13") (pin "1") (pinfunction "1_1") (pintype "passive"))
      (node (ref "U1") (pin "7") (pinfunction "NRST_7") (pintype "bidirectional"))
      (node (ref "X7") (pin "3") (pinfunction "3_3") (pintype "passive"))
    )
    (net (code "27") (name "/ONE_WIRE") (class "Default")
      (node (ref "U1") (pin "28") (pinfunction "PB2_28") (pintype "bidirectional"))
    )
    (net (code "28") (name "/OUT_1_MCU") (class "Default")
      (node (ref "U1") (pin "50") (pinfunction "PA15_50") (pintype "bidirectional"))
    )
    (net (code "29") (name "/POWER_KEY") (class "Default")
      (node (ref "U1") (pin "61") (pinfunction "PB8_61") (pintype "bidirectional"))
      (node (ref "VT7") (pin "1") (pinfunction "B_1") (pintype "passive"))
    )
    (net (code "30") (name "/RS485_RX") (class "Default")
      (node (ref "U1") (pin "53") (pinfunction "PC12_53") (pintype "bidirectional"))
    )
    (net (code "31") (name "/RS485_TE") (class "Default")
      (node (ref "U1") (pin "45") (pinfunction "PA12_45") (pintype "bidirectional"))
    )
    (net (code "32") (name "/RS485_TX") (class "Default")
      (node (ref "U1") (pin "54") (pinfunction "PD2_54") (pintype "bidirectional"))
    )
    (net (code "33") (name "/SC") (class "Default")
      (node (ref "D1") (pin "6") (pinfunction "k_6") (pintype "passive"))
      (node (ref "D6") (pin "6") (pinfunction "k_6") (pintype "passive"))
      (node (ref "R5") (pin "1") (pinfunction "1_1") (pintype "passive"))
      (node (ref "X1") (pin "11") (pinfunction "11_11") (pintype "input"))
      (node (ref "X1") (pin "3") (pinfunction "3_3") (pintype "input"))
    )
    (net (code "34") (name "/SD") (class "Default")
      (node (ref "D1") (pin "5") (pinfunction "k_5") (pintype "passive"))
      (node (ref "D6") (pin "5") (pinfunction "k_5") (pintype "passive"))
      (node (ref "R4") (pin "1") (pinfunction "1_1") (pintype "passive"))
      (node (ref "X1") (pin "15") (pinfunction "15_15") (pintype "bidirectional"))
      (node (ref "X1") (pin "7") (pinfunction "7_7") (pintype "bidirectional"))
    )
    (net (code "35") (name "/SIM_SELECT") (class "Default")
      (node (ref "U1") (pin "62") (pinfunction "PB9_62") (pintype "bidirectional"))
      (node (ref "VT1") (pin "1") (pinfunction "B_1") (pintype "passive"))
      (node (ref "VT2") (pin "1") (pinfunction "B_1") (pintype "passive"))
    )
    (net (code "36") (name "/SR") (class "Default")
      (node (ref "D1") (pin "4") (pinfunction "k_4") (pintype "passive"))
      (node (ref "D6") (pin "4") (pinfunction "k_4") (pintype "passive"))
      (node (ref "R2") (pin "2") (pinfunction "2_2") (pintype "passive"))
      (node (ref "R3") (pin "2") (pinfunction "2_2") (pintype "passive"))
      (node (ref "R7") (pin "1") (pinfunction "1_1") (pintype "passive"))
    )
    (net (code "37") (name "/SVDD") (class "Default")
      (node (ref "C1") (pin "1") (pinfunction "1_1") (pintype "passive"))
      (node (ref "C2") (pin "1") (pinfunction "1_1") (pintype "passive"))
      (node (ref "C32") (pin "2") (pinfunction "2_2") (pintype "passive"))
      (node (ref "D1") (pin "1") (pinfunction "k_1") (pintype "passive"))
      (node (ref "D2") (pin "18") (pinfunction "SIM_VDD_18") (pintype "power_in"))
      (node (ref "D6") (pin "1") (pinfunction "k_1") (pintype "passive"))
      (node (ref "R6") (pin "1") (pinfunction "1_1") (pintype "passive"))
      (node (ref "X1") (pin "1") (pinfunction "1_1") (pintype "power_in"))
      (node (ref "X1") (pin "9") (pinfunction "9_9") (pintype "power_in"))
    )
    (net (code "38") (name "/SWCLK") (class "Default")
      (node (ref "U1") (pin "49") (pinfunction "PA14_49") (pintype "bidirectional"))
      (node (ref "X7") (pin "2") (pinfunction "2_2") (pintype "passive"))
    )
    (net (code "39") (name "/SWDIO") (class "Default")
      (node (ref "U1") (pin "46") (pinfunction "PA13_46") (pintype "bidirectional"))
      (node (ref "X7") (pin "4") (pinfunction "4_4") (pintype "passive"))
    )
    (net (code "40") (name "/SWO") (class "Default")
      (node (ref "U1") (pin "55") (pinfunction "PB3_55") (pintype "bidirectional"))
      (node (ref "X7") (pin "5") (pinfunction "5_5") (pintype "passive"))
    )
    (net (code "41") (name "/UPOW_ADC") (class "Default")
      (node (ref "U1") (pin "9") (pinfunction "PC1_9") (pintype "bidirectional"))
    )
    (net (code "42") (name "GND") (class "Default")
      (node (ref "A1") (pin "12") (pinfunction "GND_12") (pintype "power_in"))
      (node (ref "A1") (pin "3") (pinfunction "GND_3") (pintype "power_in"))
      (node (ref "C1") (pin "2") (pinfunction "2_2") (pintype "passive"))
      (node (ref "C10") (pin "1") (pinfunction "1_1") (pintype "passive"))
      (node (ref "C11") (pin "1") (pinfunction "1_1") (pintype "passive"))
      (node (ref "C12") (pin "1") (pinfunction "1_1") (pintype "passive"))
      (node (ref "C13") (pin "1") (pinfunction "1_1") (pintype "passive"))
      (node (ref "C14") (pin "1") (pinfunction "1_1") (pintype "passive"))
      (node (ref "C15") (pin "1") (pinfunction "1_1") (pintype "passive"))
      (node (ref "C16") (pin "1") (pinfunction "1_1") (pintype "passive"))
      (node (ref "C17") (pin "1") (pinfunction "1_1") (pintype "passive"))
      (node (ref "C18") (pin "1") (pinfunction "1_1") (pintype "passive"))
      (node (ref "C19") (pin "1") (pinfunction "1_1") (pintype "passive"))
      (node (ref "C2") (pin "2") (pinfunction "2_2") (pintype "passive"))
      (node (ref "C20") (pin "1") (pinfunction "1_1") (pintype "passive"))
      (node (ref "C3") (pin "2") (pinfunction "2_2") (pintype "passive"))
      (node (ref "C32") (pin "1") (pinfunction "1_1") (pintype "passive"))
      (node (ref "C4") (pin "1") (pinfunction "1_1") (pintype "passive"))
      (node (ref "C5") (pin "2") (pinfunction "2_2") (pintype "passive"))
      (node (ref "C6") (pin "2") (pinfunction "2_2") (pintype "passive"))
      (node (ref "C7") (pin "1") (pinfunction "1_1") (pintype "passive"))
      (node (ref "C9") (pin "1") (pinfunction "1_1") (pintype "passive"))
      (node (ref "D1") (pin "2") (pinfunction "k_2") (pintype "passive"))
      (node (ref "D2") (pin "13") (pinfunction "GND_13") (pintype "power_in"))
      (node (ref "D2") (pin "19") (pinfunction "GND_19") (pintype "power_in"))
      (node (ref "D2") (pin "21") (pinfunction "GND_21") (pintype "power_in"))
      (node (ref "D2") (pin "27") (pinfunction "GND_27") (pintype "power_in"))
      (node (ref "D2") (pin "30") (pinfunction "GND_30") (pintype "power_in"))
      (node (ref "D2") (pin "31") (pinfunction "GND_31") (pintype "power_in"))
      (node (ref "D2") (pin "33") (pinfunction "GND_33") (pintype "power_in"))
      (node (ref "D2") (pin "36") (pinfunction "GND_36") (pintype "power_in"))
      (node (ref "D2") (pin "37") (pinfunction "GND_37") (pintype "power_in"))
      (node (ref "D2") (pin "8") (pinfunction "GND_8") (pintype "power_in"))
      (node (ref "D3") (pin "7") (pinfunction "GND_7") (pintype "passive"))
      (node (ref "D6") (pin "2") (pinfunction "k_2") (pintype "passive"))
      (node (ref "DD1") (pin "4") (pinfunction "GND_4") (pintype "passive"))
      (node (ref "U1") (pin "12") (pinfunction "VSSA_12") (pintype "power_in"))
      (node (ref "U1") (pin "18") (pinfunction "VSS_4_18") (pintype "power_in"))
      (node (ref "U1") (pin "31") (pinfunction "VSS_1_31") (pintype "power_in"))
      (node (ref "U1") (pin "47") (pinfunction "VSS_2_47") (pintype "power_in"))
      (node (ref "U1") (pin "60") (pinfunction "BOOT0_60") (pintype "input"))
      (node (ref "U1") (pin "63") (pinfunction "VSS_3_63") (pintype "power_in"))
      (node (ref "VD2") (pin "2") (pinfunction "K_2") (pintype "passive"))
      (node (ref "VD3") (pin "2") (pinfunction "K_2") (pintype "passive"))
      (node (ref "VD4") (pin "2") (pinfunction "K_2") (pintype "passive"))
      (node (ref "VD5") (pin "2") (pinfunction "K_2") (pintype "passive"))
      (node (ref "VD6") (pin "2") (pinfunction "K_2") (pintype "passive"))
      (node (ref "VT1") (pin "2") (pinfunction "E_2") (pintype "passive"))
      (node (ref "VT2") (pin "2") (pinfunction "E_2") (pintype "passive"))
      (node (ref "VT3") (pin "2") (pinfunction "E_2") (pintype "passive"))
      (node (ref "VT4") (pin "2") (pinfunction "E_2") (pintype "passive"))
      (node (ref "VT6") (pin "2") (pinfunction "E_2") (pintype "passive"))
      (node (ref "VT7") (pin "2") (pinfunction "E_2") (pintype "passive"))
      (node (ref "VT9") (pin "2") (pinfunction "E_2") (pintype "passive"))
      (node (ref "X1") (pin "13") (pinfunction "13_13") (pintype "power_in"))
      (node (ref "X1") (pin "17") (pinfunction "17_17") (pintype "power_in"))
      (node (ref "X1") (pin "18") (pinfunction "18_18") (pintype "power_in"))
      (node (ref "X1") (pin "19") (pinfunction "19_19") (pintype "power_in"))
      (node (ref "X1") (pin "20") (pinfunction "20_20") (pintype "power_in"))
      (node (ref "X1") (pin "5") (pinfunction "5_5") (pintype "power_in"))
      (node (ref "X2") (pin "1") (pinfunction "1_1") (pintype "passive"))
      (node (ref "X7") (pin "6") (pinfunction "6_6") (pintype "passive"))
    )
    (net (code "43") (name "Net-(D2-BT_ANT)") (class "Default")
      (node (ref "D2") (pin "20") (pinfunction "BT_ANT_20") (pintype "bidirectional"))
      (node (ref "X4") (pin "1") (pinfunction "1_1") (pintype "passive"))
    )
    (net (code "44") (name "Net-(D2-GSM_ANT)") (class "Default")
      (node (ref "D2") (pin "32") (pinfunction "GSM_ANT_32") (pintype "bidirectional"))
      (node (ref "X3") (pin "1") (pinfunction "1_1") (pintype "passive"))
    )
    (net (code "45") (name "Net-(D2-PWRKEY)") (class "Default")
      (node (ref "D2") (pin "39") (pinfunction "PWRKEY_39") (pintype "input"))
      (node (ref "VT7") (pin "3") (pinfunction "C_3") (pintype "passive"))
    )
    (net (code "46") (name "Net-(D2-SIM_CLK)") (class "Default")
      (node (ref "D2") (pin "16") (pinfunction "SIM_CLK_16") (pintype "output"))
      (node (ref "R5") (pin "2") (pinfunction "2_2") (pintype "passive"))
    )
    (net (code "47") (name "Net-(D2-SIM_DATA)") (class "Default")
      (node (ref "D2") (pin "15") (pinfunction "SIM_DATA_15") (pintype "bidirectional"))
      (node (ref "R4") (pin "2") (pinfunction "2_2") (pintype "passive"))
      (node (ref "R6") (pin "2") (pinfunction "2_2") (pintype "passive"))
    )
    (net (code "48") (name "Net-(D2-SIM_RST)") (class "Default")
      (node (ref "D2") (pin "17") (pinfunction "SIM_RST_17") (pintype "output"))
      (node (ref "R7") (pin "2") (pinfunction "2_2") (pintype "passive"))
    )
    (net (code "49") (name "Net-(D2-UART1_RXD)") (class "Default")
      (node (ref "D2") (pin "2") (pinfunction "UART1_RXD_2") (pintype "input"))
      (node (ref "R10") (pin "1") (pinfunction "1_1") (pintype "passive"))
      (node (ref "VD1") (pin "1") (pinfunction "A_1") (pintype "passive"))
    )
    (net (code "50") (name "Net-(D2-UART1_TXD)") (class "Default")
      (node (ref "D2") (pin "1") (pinfunction "UART1_TXD_1") (pintype "output"))
      (node (ref "R11") (pin "2") (pinfunction "2_2") (pintype "passive"))
    )
    (net (code "51") (name "Net-(D2-VRTC)") (class "Default")
      (node (ref "C3") (pin "1") (pinfunction "1_1") (pintype "passive"))
      (node (ref "D2") (pin "28") (pinfunction "VRTC_28") (pintype "power_in"))
    )
    (net (code "52") (name "Net-(D3-SO)") (class "Default")
      (node (ref "D3") (pin "8") (pinfunction "SO_8") (pintype "passive"))
      (node (ref "R19") (pin "2") (pinfunction "2_2") (pintype "passive"))
    )
    (net (code "53") (name "Net-(DD1-SO)") (class "Default")
      (node (ref "DD1") (pin "2") (pinfunction "SO_2") (pintype "passive"))
      (node (ref "R14") (pin "2") (pinfunction "2_2") (pintype "passive"))
    )
    (net (code "54") (name "Net-(U1A-PB10)") (class "Default")
      (node (ref "U1") (pin "29") (pinfunction "PB10_29") (pintype "bidirectional"))
      (node (ref "X25") (pin "1") (pinfunction "1_1") (pintype "passive"))
    )
    (net (code "55") (name "Net-(U1A-PB11)") (class "Default")
      (node (ref "U1") (pin "30") (pinfunction "PB11_30") (pintype "bidirectional"))
      (node (ref "X26") (pin "1") (pinfunction "1_1") (pintype "passive"))
    )
    (net (code "56") (name "Net-(U1A-PD0-OSC_IN)") (class "Default")
      (node (ref "C12") (pin "2") (pinfunction "2_2") (pintype "passive"))
      (node (ref "U1") (pin "5") (pinfunction "PD0-OSC_IN_5") (pintype "bidirectional"))
      (node (ref "Y1") (pin "2") (pinfunction "OSC2_2") (pintype "passive"))
    )
    (net (code "57") (name "Net-(U1A-PD1)") (class "Default")
      (node (ref "C13") (pin "2") (pinfunction "2_2") (pintype "passive"))
      (node (ref "U1") (pin "6") (pinfunction "PD1_6") (pintype "bidirectional"))
      (node (ref "Y1") (pin "1") (pinfunction "OSC1_1") (pintype "passive"))
    )
    (net (code "58") (name "Net-(U1B-VDDA)") (class "Default")
      (node (ref "C10") (pin "2") (pinfunction "2_2") (pintype "passive"))
      (node (ref "C9") (pin "2") (pinfunction "2_2") (pintype "passive"))
      (node (ref "L2") (pin "2") (pinfunction "2_2") (pintype "passive"))
      (node (ref "U1") (pin "13") (pinfunction "VDDA_13") (pintype "power_in"))
    )
    (net (code "59") (name "Net-(VD2-A)") (class "Default")
      (node (ref "R17") (pin "2") (pinfunction "2_2") (pintype "passive"))
      (node (ref "VD2") (pin "1") (pinfunction "A_1") (pintype "passive"))
    )
    (net (code "60") (name "Net-(VD3-A)") (class "Default")
      (node (ref "R18") (pin "2") (pinfunction "2_2") (pintype "passive"))
      (node (ref "VD3") (pin "1") (pinfunction "A_1") (pintype "passive"))
    )
    (net (code "61") (name "Net-(VD4-A)") (class "Default")
      (node (ref "R20") (pin "2") (pinfunction "2_2") (pintype "passive"))
      (node (ref "VD4") (pin "1") (pinfunction "A_1") (pintype "passive"))
    )
    (net (code "62") (name "Net-(VD5-A)") (class "Default")
      (node (ref "R21") (pin "2") (pinfunction "2_2") (pintype "passive"))
      (node (ref "VD5") (pin "1") (pinfunction "A_1") (pintype "passive"))
    )
    (net (code "63") (name "Net-(VD6-A)") (class "Default")
      (node (ref "R22") (pin "2") (pinfunction "2_2") (pintype "passive"))
      (node (ref "VD6") (pin "1") (pinfunction "A_1") (pintype "passive"))
    )
    (net (code "64") (name "Net-(VD7-A)") (class "Default")
      (node (ref "R23") (pin "1") (pinfunction "1_1") (pintype "passive"))
      (node (ref "VD7") (pin "1") (pinfunction "A_1") (pintype "passive"))
    )
    (net (code "65") (name "Net-(VT1-C)") (class "Default")
      (node (ref "R1") (pin "2") (pinfunction "2_2") (pintype "passive"))
      (node (ref "VT1") (pin "3") (pinfunction "C_3") (pintype "passive"))
      (node (ref "VT4") (pin "1") (pinfunction "B_1") (pintype "passive"))
    )
    (net (code "66") (name "Net-(VT2-C)") (class "Default")
      (node (ref "R2") (pin "1") (pinfunction "1_1") (pintype "passive"))
      (node (ref "VT2") (pin "3") (pinfunction "C_3") (pintype "passive"))
      (node (ref "X1") (pin "10") (pinfunction "10_10") (pintype "input"))
    )
    (net (code "67") (name "Net-(VT4-C)") (class "Default")
      (node (ref "R3") (pin "1") (pinfunction "1_1") (pintype "passive"))
      (node (ref "VT4") (pin "3") (pinfunction "C_3") (pintype "passive"))
      (node (ref "X1") (pin "2") (pinfunction "2_2") (pintype "input"))
    )
    (net (code "68") (name "Net-(VT5-G)") (class "Default")
      (node (ref "R9") (pin "1") (pinfunction "1_1") (pintype "passive"))
      (node (ref "VT5") (pin "1") (pinfunction "G_1") (pintype "passive"))
      (node (ref "VT6") (pin "3") (pinfunction "C_3") (pintype "passive"))
    )
    (net (code "69") (name "Net-(VT8-G)") (class "Default")
      (node (ref "C8") (pin "1") (pinfunction "1_1") (pintype "passive"))
      (node (ref "R12") (pin "1") (pinfunction "1_1") (pintype "passive"))
      (node (ref "VT8") (pin "1") (pinfunction "G_1") (pintype "passive"))
      (node (ref "VT9") (pin "3") (pinfunction "C_3") (pintype "passive"))
    )
    (net (code "70") (name "VDD_EXT") (class "Default")
      (node (ref "D2") (pin "40") (pinfunction "VDD_EXT_40") (pintype "power_in"))
      (node (ref "R10") (pin "2") (pinfunction "2_2") (pintype "passive"))
    )
    (net (code "71") (name "unconnected-(A1-1PPS-Pad6)") (class "Default")
      (node (ref "A1") (pin "6") (pinfunction "1PPS_6") (pintype "output"))
    )
    (net (code "72") (name "unconnected-(A1-EXT_ANT-Pad11)") (class "Default")
      (node (ref "A1") (pin "11") (pinfunction "EXT_ANT_11") (pintype "input"))
    )
    (net (code "73") (name "unconnected-(A1-NC-Pad8)") (class "Default")
      (node (ref "A1") (pin "8") (pinfunction "NC_8") (pintype "output"))
    )
    (net (code "74") (name "unconnected-(A1-NC-Pad9)") (class "Default")
      (node (ref "A1") (pin "9") (pinfunction "NC_9") (pintype "output"))
    )
    (net (code "75") (name "unconnected-(A1-RESET-Pad10)") (class "Default")
      (node (ref "A1") (pin "10") (pinfunction "RESET_10") (pintype "input"))
    )
    (net (code "76") (name "unconnected-(A1-RXD1-Pad1)") (class "Default")
      (node (ref "A1") (pin "1") (pinfunction "RXD1_1") (pintype "input"))
    )
    (net (code "77") (name "unconnected-(A1-TIMER-Pad7)") (class "Default")
      (node (ref "A1") (pin "7") (pinfunction "TIMER_7") (pintype "output"))
    )
    (net (code "78") (name "unconnected-(D1-k-Pad3)") (class "Default")
      (node (ref "D1") (pin "3") (pinfunction "k_3") (pintype "passive"))
    )
    (net (code "79") (name "unconnected-(D2-ADC-Pad38)") (class "Default")
      (node (ref "D2") (pin "38") (pinfunction "ADC_38") (pintype "input"))
    )
    (net (code "80") (name "unconnected-(D2-MIC_N-Pad10)") (class "Default")
      (node (ref "D2") (pin "10") (pinfunction "MIC_N_10") (pintype "input"))
    )
    (net (code "81") (name "unconnected-(D2-MIC_P-Pad9)") (class "Default")
      (node (ref "D2") (pin "9") (pinfunction "MIC_P_9") (pintype "input"))
    )
    (net (code "82") (name "unconnected-(D2-RF_SYNC-Pad29)") (class "Default")
      (node (ref "D2") (pin "29") (pinfunction "RF_SYNC_29") (pintype "output"))
    )
    (net (code "83") (name "unconnected-(D2-SIM_DET-Pad14)") (class "Default")
      (node (ref "D2") (pin "14") (pinfunction "SIM_DET_14") (pintype "input"))
    )
    (net (code "84") (name "unconnected-(D2-SPK_N-Pad12)") (class "Default")
      (node (ref "D2") (pin "12") (pinfunction "SPK_N_12") (pintype "output"))
    )
    (net (code "85") (name "unconnected-(D2-SPK_P-Pad11)") (class "Default")
      (node (ref "D2") (pin "11") (pinfunction "SPK_P_11") (pintype "output"))
    )
    (net (code "86") (name "unconnected-(D2-UART1_CTS-Pad4)") (class "Default")
      (node (ref "D2") (pin "4") (pinfunction "UART1_CTS_4") (pintype "output"))
    )
    (net (code "87") (name "unconnected-(D2-UART1_DCD-Pad5)") (class "Default")
      (node (ref "D2") (pin "5") (pinfunction "UART1_DCD_5") (pintype "output"))
    )
    (net (code "88") (name "unconnected-(D2-UART1_DTR-Pad6)") (class "Default")
      (node (ref "D2") (pin "6") (pinfunction "UART1_DTR_6") (pintype "input"))
    )
    (net (code "89") (name "unconnected-(D2-UART1_RI-Pad7)") (class "Default")
      (node (ref "D2") (pin "7") (pinfunction "UART1_RI_7") (pintype "output"))
    )
    (net (code "90") (name "unconnected-(D2-UART1_RTS-Pad3)") (class "Default")
      (node (ref "D2") (pin "3") (pinfunction "UART1_RTS_3") (pintype "input"))
    )
    (net (code "91") (name "unconnected-(D2-UART2_RXD-Pad23)") (class "Default")
      (node (ref "D2") (pin "23") (pinfunction "UART2_RXD_23") (pintype "input"))
    )
    (net (code "92") (name "unconnected-(D2-UART2_TXD-Pad22)") (class "Default")
      (node (ref "D2") (pin "22") (pinfunction "UART2_TXD_22") (pintype "output"))
    )
    (net (code "93") (name "unconnected-(D2-USB_DM-Pad26)") (class "Default")
      (node (ref "D2") (pin "26") (pinfunction "USB_DM_26") (pintype "bidirectional"))
    )
    (net (code "94") (name "unconnected-(D2-USB_DP-Pad25)") (class "Default")
      (node (ref "D2") (pin "25") (pinfunction "USB_DP_25") (pintype "bidirectional"))
    )
    (net (code "95") (name "unconnected-(D2-USB_VBUS-Pad24)") (class "Default")
      (node (ref "D2") (pin "24") (pinfunction "USB_VBUS_24") (pintype "input"))
    )
    (net (code "96") (name "unconnected-(D6-k-Pad3)") (class "Default")
      (node (ref "D6") (pin "3") (pinfunction "k_3") (pintype "passive"))
    )
    (net (code "97") (name "unconnected-(U1A-PA8-Pad41)") (class "Default")
      (node (ref "U1") (pin "41") (pinfunction "PA8_41") (pintype "bidirectional"))
    )
    (net (code "98") (name "unconnected-(U1A-PA9-Pad42)") (class "Default")
      (node (ref "U1") (pin "42") (pinfunction "PA9_42") (pintype "bidirectional"))
    )
    (net (code "99") (name "unconnected-(U1A-PA10-Pad43)") (class "Default")
      (node (ref "U1") (pin "43") (pinfunction "PA10_43") (pintype "bidirectional"))
    )
    (net (code "100") (name "unconnected-(U1A-PB0-Pad26)") (class "Default")
      (node (ref "U1") (pin "26") (pinfunction "PB0_26") (pintype "bidirectional"))
    )
    (net (code "101") (name "unconnected-(U1A-PB1-Pad27)") (class "Default")
      (node (ref "U1") (pin "27") (pinfunction "PB1_27") (pintype "bidirectional"))
    )
    (net (code "102") (name "unconnected-(U1A-PB12-Pad33)") (class "Default")
      (node (ref "U1") (pin "33") (pinfunction "PB12_33") (pintype "bidirectional"))
    )
    (net (code "103") (name "unconnected-(U1A-PB13-Pad34)") (class "Default")
      (node (ref "U1") (pin "34") (pinfunction "PB13_34") (pintype "bidirectional"))
    )
    (net (code "104") (name "unconnected-(U1A-PB14-Pad35)") (class "Default")
      (node (ref "U1") (pin "35") (pinfunction "PB14_35") (pintype "bidirectional"))
    )
    (net (code "105") (name "unconnected-(U1A-PB15-Pad36)") (class "Default")
      (node (ref "U1") (pin "36") (pinfunction "PB15_36") (pintype "bidirectional"))
    )
    (net (code "106") (name "unconnected-(U1A-PC4-Pad24)") (class "Default")
      (node (ref "U1") (pin "24") (pinfunction "PC4_24") (pintype "bidirectional"))
    )
    (net (code "107") (name "unconnected-(U1A-PC5-Pad25)") (class "Default")
      (node (ref "U1") (pin "25") (pinfunction "PC5_25") (pintype "bidirectional"))
    )
    (net (code "108") (name "unconnected-(U1A-PC6-Pad37)") (class "Default")
      (node (ref "U1") (pin "37") (pinfunction "PC6_37") (pintype "bidirectional"))
    )
    (net (code "109") (name "unconnected-(U1A-PC10-Pad51)") (class "Default")
      (node (ref "U1") (pin "51") (pinfunction "PC10_51") (pintype "bidirectional"))
    )
    (net (code "110") (name "unconnected-(U1A-PC13-TAMPER-RTC-Pad2)") (class "Default")
      (node (ref "U1") (pin "2") (pinfunction "PC13-TAMPER-RTC_2") (pintype "bidirectional"))
    )
    (net (code "111") (name "unconnected-(U1A-PC14-OSC32_IN-Pad3)") (class "Default")
      (node (ref "U1") (pin "3") (pinfunction "PC14-OSC32_IN_3") (pintype "bidirectional"))
    )
    (net (code "112") (name "unconnected-(U1A-PC15-OSC32_OUT-Pad4)") (class "Default")
      (node (ref "U1") (pin "4") (pinfunction "PC15-OSC32_OUT_4") (pintype "bidirectional"))
    )
    (net (code "113") (name "unconnected-(U1B-VBAT-Pad1)") (class "Default")
      (node (ref "U1") (pin "1") (pinfunction "VBAT_1") (pintype "power_in"))
    )
    (net (code "114") (name "unconnected-(X1-Pad4)") (class "Default")
      (node (ref "X1") (pin "4") (pinfunction "4_4") (pintype "passive"))
    )
    (net (code "115") (name "unconnected-(X1-Pad6)") (class "Default")
      (node (ref "X1") (pin "6") (pinfunction "6_6") (pintype "power_in"))
    )
    (net (code "116") (name "unconnected-(X1-Pad8)") (class "Default")
      (node (ref "X1") (pin "8") (pinfunction "8_8") (pintype "passive"))
    )
    (net (code "117") (name "unconnected-(X1-Pad12)") (class "Default")
      (node (ref "X1") (pin "12") (pinfunction "12_12") (pintype "passive"))
    )
    (net (code "118") (name "unconnected-(X1-Pad14)") (class "Default")
      (node (ref "X1") (pin "14") (pinfunction "14_14") (pintype "power_in"))
    )
    (net (code "119") (name "unconnected-(X1-Pad16)") (class "Default")
      (node (ref "X1") (pin "16") (pinfunction "16_16") (pintype "passive"))
    )
  )
)
